# M_O_ext_bluetooth_WT5105.net
KiCad netlist of a schematic drawn in EAGLE
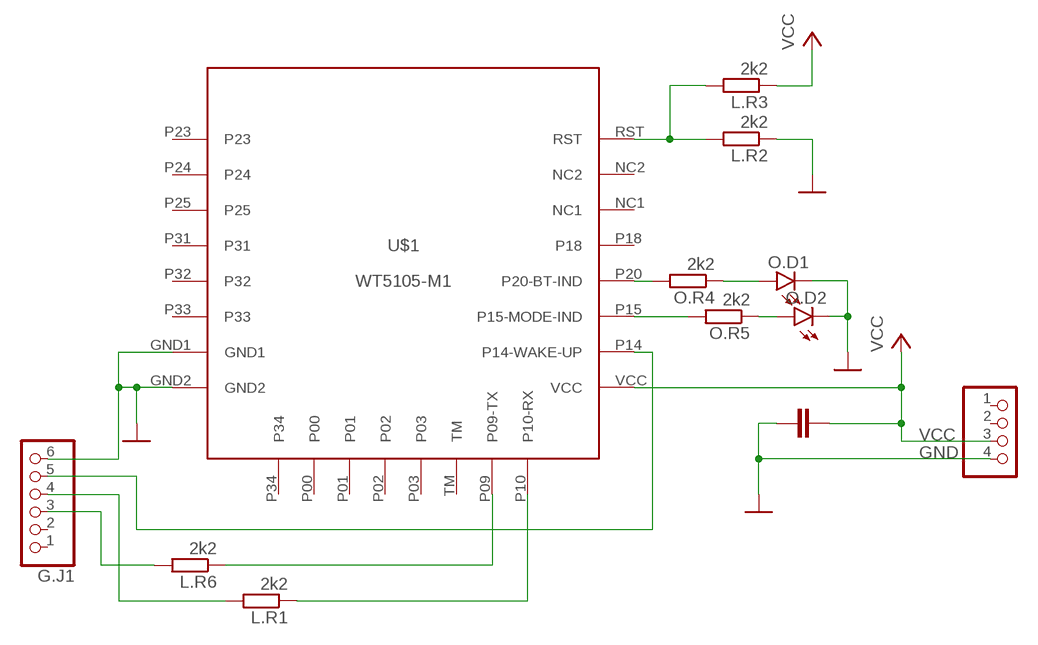
[diagram p0: schematic, sheet 1]

(export (version "E")
  (design (tool "Eeschema 10.0.6"))
  (components
    (comp (ref "G.J1")
      (value "PINHD-1X6")
      (footprint "eagle-import:1X06")
      (libsource (lib "eagle-import") (part "PINHD-1X6"))
    )
    (comp (ref "G.J2")
      (value "PINHD-1X4")
      (footprint "eagle-import:1X04")
      (libsource (lib "eagle-import") (part "PINHD-1X4"))
    )
    (comp (ref "L.C1")
      (value "100n")
      (footprint "eagle-import:C0603")
      (libsource (lib "eagle-import") (part "C-EUC0603"))
    )
    (comp (ref "L.R1")
      (value "2k2")
      (footprint "eagle-import:R0603")
      (libsource (lib "eagle-import") (part "R-EU_R0603"))
    )
    (comp (ref "L.R2")
      (value "2k2")
      (footprint "eagle-import:R0603")
      (libsource (lib "eagle-import") (part "R-EU_R0603"))
    )
    (comp (ref "L.R3")
      (value "2k2")
      (footprint "eagle-import:R0603")
      (libsource (lib "eagle-import") (part "R-EU_R0603"))
    )
    (comp (ref "L.R6")
      (value "2k2")
      (footprint "eagle-import:R0603")
      (libsource (lib "eagle-import") (part "R-EU_R0603"))
    )
    (comp (ref "O.D1")
      (value "LEDCHIP-LED0603")
      (footprint "eagle-import:CHIP-LED0603")
      (libsource (lib "eagle-import") (part "LEDCHIP-LED0603"))
    )
    (comp (ref "O.D2")
      (value "LEDCHIP-LED0603")
      (footprint "eagle-import:CHIP-LED0603")
      (libsource (lib "eagle-import") (part "LEDCHIP-LED0603"))
    )
    (comp (ref "O.R4")
      (value "2k2")
      (footprint "eagle-import:R0603")
      (libsource (lib "eagle-import") (part "R-EU_R0603"))
    )
    (comp (ref "O.R5")
      (value "2k2")
      (footprint "eagle-import:R0603")
      (libsource (lib "eagle-import") (part "R-EU_R0603"))
    )
    (comp (ref "U$1")
      (value "WT5105-M1")
      (footprint "eagle-import:WT5105-M1")
      (libsource (lib "eagle-import") (part "WT5105-M1"))
    )
  )
  (nets
    (net (code "1") (name "GND") (class "Default")
      (node (ref "G.J1") (pin "6") (pinfunction "6_6") (pintype "passive"))
      (node (ref "G.J2") (pin "4") (pinfunction "4_4") (pintype "passive"))
      (node (ref "L.C1") (pin "1") (pinfunction "1_1") (pintype "passive"))
      (node (ref "L.R2") (pin "1") (pinfunction "1_1") (pintype "passive"))
      (node (ref "O.D1") (pin "C1") (pinfunction "C_C1") (pintype "passive"))
      (node (ref "O.D2") (pin "C1") (pinfunction "C_C1") (pintype "passive"))
      (node (ref "U$1") (pin "GND1") (pinfunction "GND1_GND1") (pintype "bidirectional"))
      (node (ref "U$1") (pin "GND2") (pinfunction "GND2_GND2") (pintype "bidirectional"))
    )
    (net (code "2") (name "Net-(G.J1-Pad3)") (class "Default")
      (node (ref "G.J1") (pin "3") (pinfunction "3_3") (pintype "passive"))
      (node (ref "L.R6") (pin "2") (pinfunction "2_2") (pintype "passive"))
    )
    (net (code "3") (name "Net-(G.J1-Pad4)") (class "Default")
      (node (ref "G.J1") (pin "4") (pinfunction "4_4") (pintype "passive"))
      (node (ref "L.R1") (pin "2") (pinfunction "2_2") (pintype "passive"))
    )
    (net (code "4") (name "Net-(L.R2-Pad2)") (class "Default")
      (node (ref "L.R2") (pin "2") (pinfunction "2_2") (pintype "passive"))
      (node (ref "L.R3") (pin "2") (pinfunction "2_2") (pintype "passive"))
      (node (ref "U$1") (pin "RST") (pinfunction "RST_RST") (pintype "bidirectional"))
    )
    (net (code "5") (name "Net-(O.D1-A)") (class "Default")
      (node (ref "O.D1") (pin "A1") (pinfunction "A_A1") (pintype "passive"))
      (node (ref "O.R4") (pin "1") (pinfunction "1_1") (pintype "passive"))
    )
    (net (code "6") (name "Net-(O.D2-A)") (class "Default")
      (node (ref "O.D2") (pin "A1") (pinfunction "A_A1") (pintype "passive"))
      (node (ref "O.R5") (pin "1") (pinfunction "1_1") (pintype "passive"))
    )
    (net (code "7") (name "Net-(U$1-P09-TX)") (class "Default")
      (node (ref "L.R6") (pin "1") (pinfunction "1_1") (pintype "passive"))
      (node (ref "U$1") (pin "P09") (pinfunction "P09-TX_P09") (pintype "bidirectional"))
    )
    (net (code "8") (name "Net-(U$1-P10-RX)") (class "Default")
      (node (ref "L.R1") (pin "1") (pinfunction "1_1") (pintype "passive"))
      (node (ref "U$1") (pin "P10") (pinfunction "P10-RX_P10") (pintype "bidirectional"))
    )
    (net (code "9") (name "Net-(U$1-P14-WAKE-UP)") (class "Default")
      (node (ref "G.J1") (pin "5") (pinfunction "5_5") (pintype "passive"))
      (node (ref "U$1") (pin "P14") (pinfunction "P14-WAKE-UP_P14") (pintype "bidirectional"))
    )
    (net (code "10") (name "Net-(U$1-P15-MODE-IND)") (class "Default")
      (node (ref "O.R5") (pin "2") (pinfunction "2_2") (pintype "passive"))
      (node (ref "U$1") (pin "P15") (pinfunction "P15-MODE-IND_P15") (pintype "bidirectional"))
    )
    (net (code "11") (name "Net-(U$1-P20-BT-IND)") (class "Default")
      (node (ref "O.R4") (pin "2") (pinfunction "2_2") (pintype "passive"))
      (node (ref "U$1") (pin "P20") (pinfunction "P20-BT-IND_P20") (pintype "bidirectional"))
    )
    (net (code "12") (name "VCC") (class "Default")
      (node (ref "G.J2") (pin "3") (pinfunction "3_3") (pintype "passive"))
      (node (ref "L.C1") (pin "2") (pinfunction "2_2") (pintype "passive"))
      (node (ref "L.R3") (pin "1") (pinfunction "1_1") (pintype "passive"))
      (node (ref "U$1") (pin "VCC") (pinfunction "VCC_VCC") (pintype "bidirectional"))
    )
    (net (code "13") (name "unconnected-(G.J1-Pad1)") (class "Default")
      (node (ref "G.J1") (pin "1") (pinfunction "1_1") (pintype "passive"))
    )
    (net (code "14") (name "unconnected-(G.J1-Pad2)") (class "Default")
      (node (ref "G.J1") (pin "2") (pinfunction "2_2") (pintype "passive"))
    )
    (net (code "15") (name "unconnected-(G.J2-Pad1)") (class "Default")
      (node (ref "G.J2") (pin "1") (pinfunction "1_1") (pintype "passive"))
    )
    (net (code "16") (name "unconnected-(G.J2-Pad2)") (class "Default")
      (node (ref "G.J2") (pin "2") (pinfunction "2_2") (pintype "passive"))
    )
    (net (code "17") (name "unconnected-(U$1-PadNC1)") (class "Default")
      (node (ref "U$1") (pin "NC1") (pinfunction "NC1_NC1") (pintype "bidirectional"))
    )
    (net (code "18") (name "unconnected-(U$1-PadNC2)") (class "Default")
      (node (ref "U$1") (pin "NC2") (pinfunction "NC2_NC2") (pintype "bidirectional"))
    )
    (net (code "19") (name "unconnected-(U$1-PadP00)") (class "Default")
      (node (ref "U$1") (pin "P00") (pinfunction "P00_P00") (pintype "bidirectional"))
    )
    (net (code "20") (name "unconnected-(U$1-PadP01)") (class "Default")
      (node (ref "U$1") (pin "P01") (pinfunction "P01_P01") (pintype "bidirectional"))
    )
    (net (code "21") (name "unconnected-(U$1-PadP02)") (class "Default")
      (node (ref "U$1") (pin "P02") (pinfunction "P02_P02") (pintype "bidirectional"))
    )
    (net (code "22") (name "unconnected-(U$1-PadP03)") (class "Default")
      (node (ref "U$1") (pin "P03") (pinfunction "P03_P03") (pintype "bidirectional"))
    )
    (net (code "23") (name "unconnected-(U$1-PadP18)") (class "Default")
      (node (ref "U$1") (pin "P18") (pinfunction "P18_P18") (pintype "bidirectional"))
    )
    (net (code "24") (name "unconnected-(U$1-PadP23)") (class "Default")
      (node (ref "U$1") (pin "P23") (pinfunction "P23_P23") (pintype "bidirectional"))
    )
    (net (code "25") (name "unconnected-(U$1-PadP24)") (class "Default")
      (node (ref "U$1") (pin "P24") (pinfunction "P24_P24") (pintype "bidirectional"))
    )
    (net (code "26") (name "unconnected-(U$1-PadP25)") (class "Default")
      (node (ref "U$1") (pin "P25") (pinfunction "P25_P25") (pintype "bidirectional"))
    )
    (net (code "27") (name "unconnected-(U$1-PadP31)") (class "Default")
      (node (ref "U$1") (pin "P31") (pinfunction "P31_P31") (pintype "bidirectional"))
    )
    (net (code "28") (name "unconnected-(U$1-PadP32)") (class "Default")
      (node (ref "U$1") (pin "P32") (pinfunction "P32_P32") (pintype "bidirectional"))
    )
    (net (code "29") (name "unconnected-(U$1-PadP33)") (class "Default")
      (node (ref "U$1") (pin "P33") (pinfunction "P33_P33") (pintype "bidirectional"))
    )
    (net (code "30") (name "unconnected-(U$1-PadP34)") (class "Default")
      (node (ref "U$1") (pin "P34") (pinfunction "P34_P34") (pintype "bidirectional"))
    )
    (net (code "31") (name "unconnected-(U$1-PadTM)") (class "Default")
      (node (ref "U$1") (pin "TM") (pinfunction "TM_TM") (pintype "bidirectional"))
    )
  )
)
